# FINAL_PROJECT.net
KiCad netlist of a schematic drawn in EAGLE
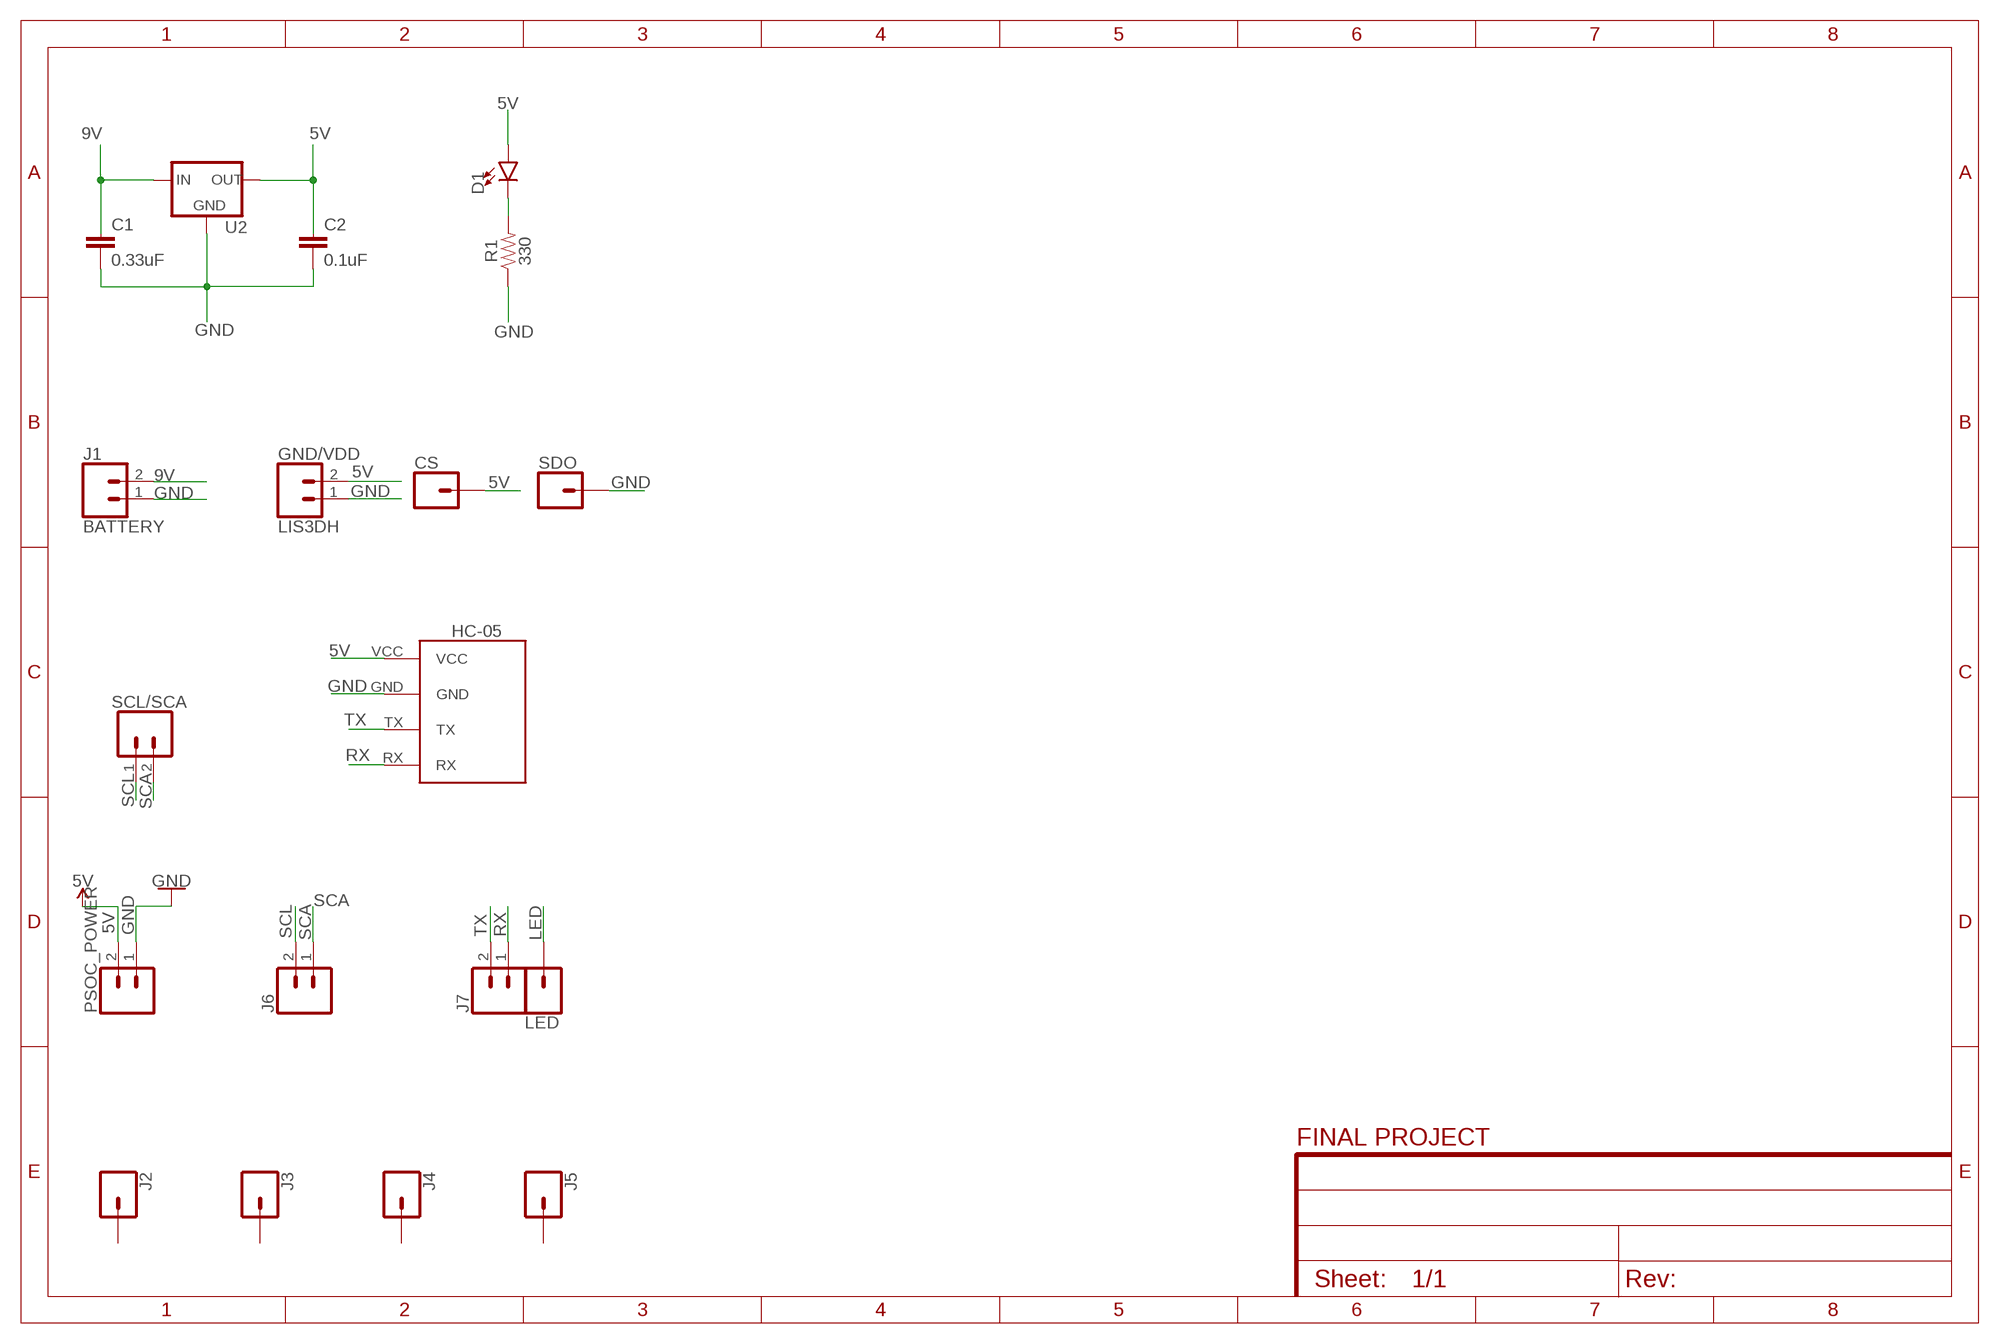
[diagram p0: schematic, sheet 1]

(export (version "E")
  (design (tool "Eeschema 10.0.6"))
  (components
    (comp (ref "C1")
      (value "0.33uF")
      (footprint "eagle-import:CAP-PTH-SMALL-KIT")
      (libsource (lib "eagle-import") (part "0.1UF-KIT-EZ-50V-20%"))
    )
    (comp (ref "C2")
      (value "0.1uF")
      (footprint "eagle-import:CAP-PTH-SMALL-KIT")
      (libsource (lib "eagle-import") (part "0.1UF-KIT-EZ-50V-20%"))
    )
    (comp (ref "CS")
      (value "CONN_01")
      (footprint "eagle-import:1X01")
      (libsource (lib "eagle-import") (part "CONN_01"))
    )
    (comp (ref "D1")
      (value "LED3MM")
      (footprint "eagle-import:LED_3MM")
      (libsource (lib "eagle-import") (part "LED3MM"))
    )
    (comp (ref "GND/VDD")
      (value "LIS3DH")
      (footprint "eagle-import:1X02")
      (libsource (lib "eagle-import") (part "CONN_02"))
    )
    (comp (ref "HC-05")
      (value "BLUETOOTH_BOARD")
      (footprint "eagle-import:BT_BOARD_FOOTPRINT")
      (libsource (lib "eagle-import") (part "BLUETOOTH_BOARD"))
    )
    (comp (ref "J1")
      (value "BATTERY")
      (footprint "eagle-import:1X02")
      (libsource (lib "eagle-import") (part "CONN_02"))
    )
    (comp (ref "J2")
      (value "CONN_01")
      (footprint "eagle-import:1X01")
      (libsource (lib "eagle-import") (part "CONN_01"))
    )
    (comp (ref "J3")
      (value "CONN_01")
      (footprint "eagle-import:1X01")
      (libsource (lib "eagle-import") (part "CONN_01"))
    )
    (comp (ref "J4")
      (value "CONN_01")
      (footprint "eagle-import:1X01")
      (libsource (lib "eagle-import") (part "CONN_01"))
    )
    (comp (ref "J5")
      (value "CONN_01")
      (footprint "eagle-import:1X01")
      (libsource (lib "eagle-import") (part "CONN_01"))
    )
    (comp (ref "J6")
      (value "CONN_02")
      (footprint "eagle-import:1X02")
      (libsource (lib "eagle-import") (part "CONN_02"))
    )
    (comp (ref "J7")
      (value "CONN_02")
      (footprint "eagle-import:1X02")
      (libsource (lib "eagle-import") (part "CONN_02"))
    )
    (comp (ref "LED")
      (value "CONN_01")
      (footprint "eagle-import:1X01")
      (libsource (lib "eagle-import") (part "CONN_01"))
    )
    (comp (ref "PSOC_POWER")
      (value "CONN_02")
      (footprint "eagle-import:1X02")
      (libsource (lib "eagle-import") (part "CONN_02"))
    )
    (comp (ref "R1")
      (value "330")
      (footprint "eagle-import:AXIAL-0.3")
      (libsource (lib "eagle-import") (part "330OHM-HORIZ-1/10W-5%"))
    )
    (comp (ref "SCL/SCA")
      (value "CONN_02")
      (footprint "eagle-import:1X02")
      (libsource (lib "eagle-import") (part "CONN_02"))
    )
    (comp (ref "SDO")
      (value "CONN_01")
      (footprint "eagle-import:1X01")
      (libsource (lib "eagle-import") (part "CONN_01"))
    )
    (comp (ref "U2")
      (value "V_REG_78XX-TO-220")
      (footprint "eagle-import:TO-220-ALT")
      (libsource (lib "eagle-import") (part "V_REG_78XX-TO-220"))
    )
  )
  (nets
    (net (code "1") (name "/9V") (class "Default")
      (node (ref "C1") (pin "1") (pinfunction "1_1") (pintype "passive"))
      (node (ref "J1") (pin "2") (pinfunction "2_2") (pintype "passive"))
      (node (ref "U2") (pin "IN") (pinfunction "IN_IN") (pintype "input"))
    )
    (net (code "2") (name "/LED") (class "Default")
      (node (ref "LED") (pin "1") (pinfunction "1_1") (pintype "passive"))
    )
    (net (code "3") (name "/RX") (class "Default")
      (node (ref "HC-05") (pin "RX") (pinfunction "RX_RX") (pintype "bidirectional"))
      (node (ref "J7") (pin "1") (pinfunction "1_1") (pintype "passive"))
    )
    (net (code "4") (name "/SCA") (class "Default")
      (node (ref "J6") (pin "1") (pinfunction "1_1") (pintype "passive"))
      (node (ref "SCL/SCA") (pin "2") (pinfunction "2_2") (pintype "passive"))
    )
    (net (code "5") (name "/SCL") (class "Default")
      (node (ref "J6") (pin "2") (pinfunction "2_2") (pintype "passive"))
      (node (ref "SCL/SCA") (pin "1") (pinfunction "1_1") (pintype "passive"))
    )
    (net (code "6") (name "/TX") (class "Default")
      (node (ref "HC-05") (pin "TX") (pinfunction "TX_TX") (pintype "bidirectional"))
      (node (ref "J7") (pin "2") (pinfunction "2_2") (pintype "passive"))
    )
    (net (code "7") (name "5V") (class "Default")
      (node (ref "C2") (pin "1") (pinfunction "1_1") (pintype "passive"))
      (node (ref "CS") (pin "1") (pinfunction "1_1") (pintype "passive"))
      (node (ref "D1") (pin "A") (pinfunction "A_A") (pintype "passive"))
      (node (ref "GND/VDD") (pin "2") (pinfunction "2_2") (pintype "passive"))
      (node (ref "HC-05") (pin "VCC") (pinfunction "VCC_VCC") (pintype "bidirectional"))
      (node (ref "PSOC_POWER") (pin "2") (pinfunction "2_2") (pintype "passive"))
      (node (ref "U2") (pin "OUT") (pinfunction "OUT_OUT") (pintype "passive"))
    )
    (net (code "8") (name "GND") (class "Default")
      (node (ref "C1") (pin "2") (pinfunction "2_2") (pintype "passive"))
      (node (ref "C2") (pin "2") (pinfunction "2_2") (pintype "passive"))
      (node (ref "GND/VDD") (pin "1") (pinfunction "1_1") (pintype "passive"))
      (node (ref "HC-05") (pin "GND") (pinfunction "GND_GND") (pintype "bidirectional"))
      (node (ref "J1") (pin "1") (pinfunction "1_1") (pintype "passive"))
      (node (ref "PSOC_POWER") (pin "1") (pinfunction "1_1") (pintype "passive"))
      (node (ref "R1") (pin "P$1") (pinfunction "1_P$1") (pintype "passive"))
      (node (ref "SDO") (pin "1") (pinfunction "1_1") (pintype "passive"))
      (node (ref "U2") (pin "GND") (pinfunction "GND_GND") (pintype "input"))
    )
    (net (code "9") (name "Net-(D1-C)") (class "Default")
      (node (ref "D1") (pin "K") (pinfunction "C_K") (pintype "passive"))
      (node (ref "R1") (pin "P$2") (pinfunction "2_P$2") (pintype "passive"))
    )
    (net (code "10") (name "unconnected-(J2-Pad1)") (class "Default")
      (node (ref "J2") (pin "1") (pinfunction "1_1") (pintype "passive"))
    )
    (net (code "11") (name "unconnected-(J3-Pad1)") (class "Default")
      (node (ref "J3") (pin "1") (pinfunction "1_1") (pintype "passive"))
    )
    (net (code "12") (name "unconnected-(J4-Pad1)") (class "Default")
      (node (ref "J4") (pin "1") (pinfunction "1_1") (pintype "passive"))
    )
    (net (code "13") (name "unconnected-(J5-Pad1)") (class "Default")
      (node (ref "J5") (pin "1") (pinfunction "1_1") (pintype "passive"))
    )
  )
)
